# DI_DO.net
KiCad netlist of a schematic drawn in Altium Designer
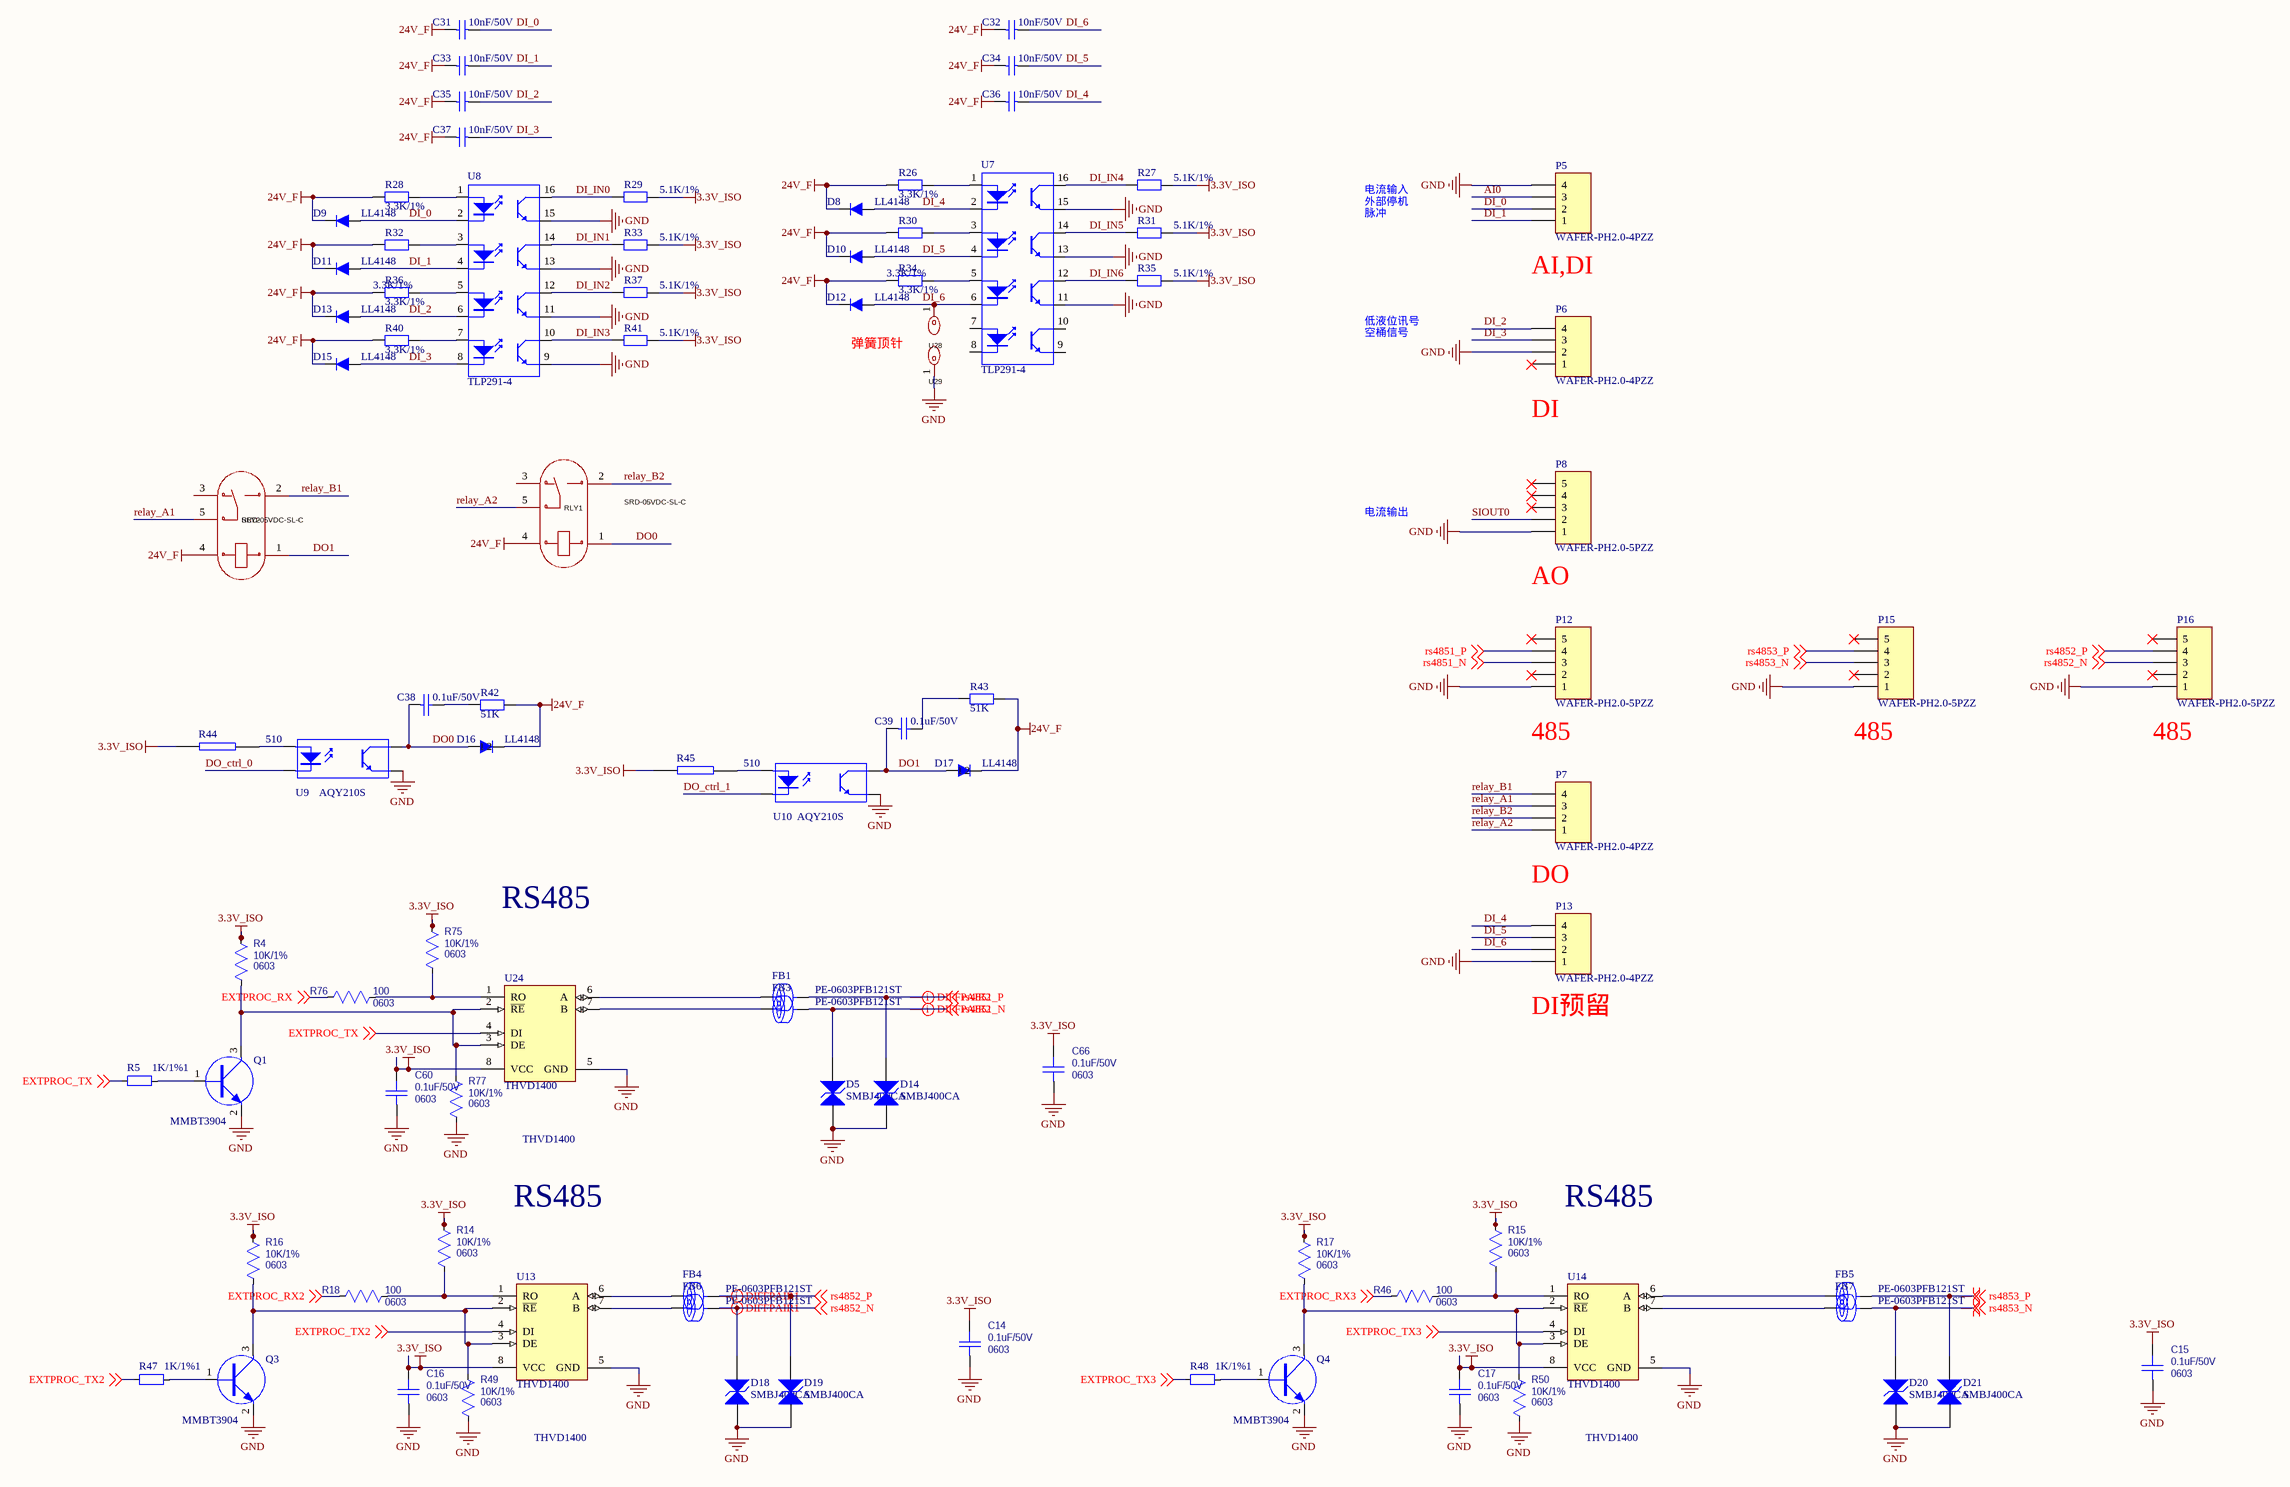
[diagram p0: DI_DO.SchDoc]

(export (version "E")
  (design (tool "Eeschema 10.0.6"))
  (components
    (comp (ref "C14")
      (value "0.1uF/50V")
      (footprint "0603C")
      (description "Capacitor, MLCC")
      (fields (field (name "PACKAGE") "0603"))
      (libsource (lib "Karl") (part "Capacitor_0603"))
    )
    (comp (ref "C15")
      (value "0.1uF/50V")
      (footprint "0603C")
      (description "Capacitor, MLCC")
      (fields (field (name "PACKAGE") "0603"))
      (libsource (lib "Karl") (part "Capacitor_0603"))
    )
    (comp (ref "C16")
      (value "0.1uF/50V")
      (footprint "0603C")
      (description "Capacitor, MLCC")
      (fields (field (name "PACKAGE") "0603"))
      (libsource (lib "Karl") (part "Capacitor_0603"))
    )
    (comp (ref "C17")
      (value "0.1uF/50V")
      (footprint "0603C")
      (description "Capacitor, MLCC")
      (fields (field (name "PACKAGE") "0603"))
      (libsource (lib "Karl") (part "Capacitor_0603"))
    )
    (comp (ref "C31")
      (value "10nF/50V")
      (footprint "0603C")
      (description "Capacitor")
      (libsource (lib "Miscellaneous Devices") (part "Cap"))
    )
    (comp (ref "C32")
      (value "10nF/50V")
      (footprint "0603C")
      (description "Capacitor")
      (libsource (lib "Miscellaneous Devices") (part "Cap"))
    )
    (comp (ref "C33")
      (value "10nF/50V")
      (footprint "0603C")
      (description "Capacitor")
      (libsource (lib "Miscellaneous Devices") (part "Cap"))
    )
    (comp (ref "C34")
      (value "10nF/50V")
      (footprint "0603C")
      (description "Capacitor")
      (libsource (lib "Miscellaneous Devices") (part "Cap"))
    )
    (comp (ref "C35")
      (value "10nF/50V")
      (footprint "0603C")
      (description "Capacitor")
      (libsource (lib "Miscellaneous Devices") (part "Cap"))
    )
    (comp (ref "C36")
      (value "10nF/50V")
      (footprint "0603C")
      (description "Capacitor")
      (libsource (lib "Miscellaneous Devices") (part "Cap"))
    )
    (comp (ref "C37")
      (value "10nF/50V")
      (footprint "0603C")
      (description "Capacitor")
      (libsource (lib "Miscellaneous Devices") (part "Cap"))
    )
    (comp (ref "C38")
      (value "0.1uF/50V")
      (footprint "0603C")
      (description "Capacitor")
      (libsource (lib "*") (part "CAP"))
    )
    (comp (ref "C39")
      (value "0.1uF/50V")
      (footprint "0603C")
      (description "Capacitor")
      (libsource (lib "*") (part "CAP"))
    )
    (comp (ref "C60")
      (value "0.1uF/50V")
      (footprint "0603C")
      (description "Capacitor, MLCC")
      (fields (field (name "PACKAGE") "0603"))
      (libsource (lib "Karl") (part "Capacitor_0603"))
    )
    (comp (ref "C66")
      (value "0.1uF/50V")
      (footprint "0603C")
      (description "Capacitor, MLCC")
      (fields (field (name "PACKAGE") "0603"))
      (libsource (lib "Karl") (part "Capacitor_0603"))
    )
    (comp (ref "D5")
      (value "SMBJ400CA")
      (footprint "SMB")
      (description "Transient Voltage Suppression Diode, 400 W, 33 V, -65 to 150 degC, 2-Pin SMD, RoHS, Tape and Reel")
      (libsource (lib "Bogen") (part "SMAJ12CA"))
    )
    (comp (ref "D8")
      (value "LL4148")
      (footprint "DO-213AB/LL34/MiniMELF")
      (description "VISHAY,LL4148,圆柱体MiniMELF100V/2A,ROHS")
      (libsource (lib "Device2018") (part "LL4148"))
    )
    (comp (ref "D9")
      (value "LL4148")
      (footprint "DO-213AB/LL34/MiniMELF")
      (description "VISHAY,LL4148,圆柱体MiniMELF100V/2A,ROHS")
      (libsource (lib "Device2018") (part "LL4148"))
    )
    (comp (ref "D10")
      (value "LL4148")
      (footprint "DO-213AB/LL34/MiniMELF")
      (description "VISHAY,LL4148,圆柱体MiniMELF100V/2A,ROHS")
      (libsource (lib "Device2018") (part "LL4148"))
    )
    (comp (ref "D11")
      (value "LL4148")
      (footprint "DO-213AB/LL34/MiniMELF")
      (description "VISHAY,LL4148,圆柱体MiniMELF100V/2A,ROHS")
      (libsource (lib "Device2018") (part "LL4148"))
    )
    (comp (ref "D12")
      (value "LL4148")
      (footprint "DO-213AB/LL34/MiniMELF")
      (description "VISHAY,LL4148,圆柱体MiniMELF100V/2A,ROHS")
      (libsource (lib "Device2018") (part "LL4148"))
    )
    (comp (ref "D13")
      (value "LL4148")
      (footprint "DO-213AB/LL34/MiniMELF")
      (description "VISHAY,LL4148,圆柱体MiniMELF100V/2A,ROHS")
      (libsource (lib "Device2018") (part "LL4148"))
    )
    (comp (ref "D14")
      (value "SMBJ400CA")
      (footprint "SMB")
      (description "Transient Voltage Suppression Diode, 400 W, 33 V, -65 to 150 degC, 2-Pin SMD, RoHS, Tape and Reel")
      (libsource (lib "Bogen") (part "SMAJ12CA"))
    )
    (comp (ref "D15")
      (value "LL4148")
      (footprint "DO-213AB/LL34/MiniMELF")
      (description "VISHAY,LL4148,圆柱体MiniMELF100V/2A,ROHS")
      (libsource (lib "Device2018") (part "LL4148"))
    )
    (comp (ref "D16")
      (value "LL4148")
      (footprint "DO-213AB/LL34/MiniMELF")
      (description "VISHAY,LL4148,圆柱体MiniMELF100V/2A,ROHS")
      (libsource (lib "") (part "LL4148_1"))
    )
    (comp (ref "D17")
      (value "LL4148")
      (footprint "DO-213AB/LL34/MiniMELF")
      (description "VISHAY,LL4148,圆柱体MiniMELF100V/2A,ROHS")
      (libsource (lib "") (part "LL4148_1"))
    )
    (comp (ref "D18")
      (value "SMBJ400CA")
      (footprint "SMB")
      (description "Transient Voltage Suppression Diode, 400 W, 33 V, -65 to 150 degC, 2-Pin SMD, RoHS, Tape and Reel")
      (libsource (lib "Bogen") (part "SMAJ12CA"))
    )
    (comp (ref "D19")
      (value "SMBJ400CA")
      (footprint "SMB")
      (description "Transient Voltage Suppression Diode, 400 W, 33 V, -65 to 150 degC, 2-Pin SMD, RoHS, Tape and Reel")
      (libsource (lib "Bogen") (part "SMAJ12CA"))
    )
    (comp (ref "D20")
      (value "SMBJ400CA")
      (footprint "SMB")
      (description "Transient Voltage Suppression Diode, 400 W, 33 V, -65 to 150 degC, 2-Pin SMD, RoHS, Tape and Reel")
      (libsource (lib "Bogen") (part "SMAJ12CA"))
    )
    (comp (ref "D21")
      (value "SMBJ400CA")
      (footprint "SMB")
      (description "Transient Voltage Suppression Diode, 400 W, 33 V, -65 to 150 degC, 2-Pin SMD, RoHS, Tape and Reel")
      (libsource (lib "Bogen") (part "SMAJ12CA"))
    )
    (comp (ref "FB1")
      (value "PE-0603PFB121ST")
      (footprint "FBC0603")
      (description "Ferrite Bead Chip")
      (libsource (lib "Karl") (part "FBC0603"))
    )
    (comp (ref "FB3")
      (value "PE-0603PFB121ST")
      (footprint "FBC0603")
      (description "Ferrite Bead Chip")
      (libsource (lib "Karl") (part "FBC0603"))
    )
    (comp (ref "FB4")
      (value "PE-0603PFB121ST")
      (footprint "FBC0603")
      (description "Ferrite Bead Chip")
      (libsource (lib "Karl") (part "FBC0603"))
    )
    (comp (ref "FB5")
      (value "PE-0603PFB121ST")
      (footprint "FBC0603")
      (description "Ferrite Bead Chip")
      (libsource (lib "Karl") (part "FBC0603"))
    )
    (comp (ref "FB6")
      (value "PE-0603PFB121ST")
      (footprint "FBC0603")
      (description "Ferrite Bead Chip")
      (libsource (lib "Karl") (part "FBC0603"))
    )
    (comp (ref "FB7")
      (value "PE-0603PFB121ST")
      (footprint "FBC0603")
      (description "Ferrite Bead Chip")
      (libsource (lib "Karl") (part "FBC0603"))
    )
    (comp (ref "P5")
      (value "WAFER-PH2.0-4PZZ")
      (footprint "CONN#PH2.0-4A")
      (description "Header, 4-Pin")
      (libsource (lib "Miscellaneous Connectors") (part "Header 4"))
    )
    (comp (ref "P6")
      (value "WAFER-PH2.0-4PZZ")
      (footprint "CONN#PH2.0-4A")
      (description "Header, 4-Pin")
      (libsource (lib "Miscellaneous Connectors") (part "Header 4"))
    )
    (comp (ref "P7")
      (value "WAFER-PH2.0-4PZZ")
      (footprint "CONN#PH2.0-4A")
      (description "Header, 4-Pin")
      (libsource (lib "Miscellaneous Connectors") (part "Header 4"))
    )
    (comp (ref "P8")
      (value "WAFER-PH2.0-5PZZ")
      (footprint "CONN#PH2.0-5A")
      (description "Header, 5-Pin")
      (libsource (lib "Miscellaneous Connectors") (part "Header 5"))
    )
    (comp (ref "P12")
      (value "WAFER-PH2.0-5PZZ")
      (footprint "CONN#PH2.0-5A")
      (description "Header, 5-Pin")
      (libsource (lib "Miscellaneous Connectors") (part "Header 5"))
    )
    (comp (ref "P13")
      (value "WAFER-PH2.0-4PZZ")
      (footprint "CONN#PH2.0-4A")
      (description "Header, 4-Pin")
      (libsource (lib "Miscellaneous Connectors") (part "Header 4"))
    )
    (comp (ref "P15")
      (value "WAFER-PH2.0-5PZZ")
      (footprint "CONN#PH2.0-5A")
      (description "Header, 5-Pin")
      (libsource (lib "Miscellaneous Connectors") (part "Header 5"))
    )
    (comp (ref "P16")
      (value "WAFER-PH2.0-5PZZ")
      (footprint "CONN#PH2.0-5A")
      (description "Header, 5-Pin")
      (libsource (lib "Miscellaneous Connectors") (part "Header 5"))
    )
    (comp (ref "Q1")
      (value "MMBT3904")
      (footprint "SOT23-3")
      (libsource (lib "CenLib") (part "NPN_MMBT3904"))
    )
    (comp (ref "Q3")
      (value "MMBT3904")
      (footprint "SOT23-3")
      (libsource (lib "CenLib") (part "NPN_MMBT3904"))
    )
    (comp (ref "Q4")
      (value "MMBT3904")
      (footprint "SOT23-3")
      (libsource (lib "CenLib") (part "NPN_MMBT3904"))
    )
    (comp (ref "R4")
      (value "10K/1%")
      (footprint "0603R")
      (description "Resistor, Standard")
      (fields (field (name "PACKAGE") "0603"))
      (libsource (lib "Karl") (part "Resistor_0603"))
    )
    (comp (ref "R5") (value "1K/1%1") (footprint "0603r") (libsource (lib "RC_M_D_00") (part "RES0603")))
    (comp (ref "R14")
      (value "10K/1%")
      (footprint "0603R")
      (description "Resistor, Standard")
      (fields (field (name "PACKAGE") "0603"))
      (libsource (lib "Karl") (part "Resistor_0603"))
    )
    (comp (ref "R15")
      (value "10K/1%")
      (footprint "0603R")
      (description "Resistor, Standard")
      (fields (field (name "PACKAGE") "0603"))
      (libsource (lib "Karl") (part "Resistor_0603"))
    )
    (comp (ref "R16")
      (value "10K/1%")
      (footprint "0603R")
      (description "Resistor, Standard")
      (fields (field (name "PACKAGE") "0603"))
      (libsource (lib "Karl") (part "Resistor_0603"))
    )
    (comp (ref "R17")
      (value "10K/1%")
      (footprint "0603R")
      (description "Resistor, Standard")
      (fields (field (name "PACKAGE") "0603"))
      (libsource (lib "Karl") (part "Resistor_0603"))
    )
    (comp (ref "R18")
      (value "100")
      (footprint "0603R")
      (description "Resistor, Standard")
      (fields (field (name "PACKAGE") "0603"))
      (libsource (lib "Karl") (part "Resistor_0603"))
    )
    (comp (ref "R26") (value "3.3K/1%") (footprint "0603R") (libsource (lib "MQlibrary") (part "Res0805M")))
    (comp (ref "R27") (value "5.1K/1%") (footprint "0603R") (libsource (lib "MQlibrary") (part "Res0805M")))
    (comp (ref "R28") (value "3.3K/1%") (footprint "0603R") (libsource (lib "MQlibrary") (part "Res0805M")))
    (comp (ref "R29") (value "5.1K/1%") (footprint "0603R") (libsource (lib "MQlibrary") (part "Res0805M")))
    (comp (ref "R30") (value "3.3K/1%") (footprint "0603R") (libsource (lib "MQlibrary") (part "Res0805M")))
    (comp (ref "R31") (value "5.1K/1%") (footprint "0603R") (libsource (lib "MQlibrary") (part "Res0805M")))
    (comp (ref "R32") (value "3.3K/1%") (footprint "0603R") (libsource (lib "MQlibrary") (part "Res0805M")))
    (comp (ref "R33") (value "5.1K/1%") (footprint "0603R") (libsource (lib "MQlibrary") (part "Res0805M")))
    (comp (ref "R34") (value "3.3K/1%") (footprint "0603R") (libsource (lib "MQlibrary") (part "Res0805M")))
    (comp (ref "R35") (value "5.1K/1%") (footprint "0603R") (libsource (lib "MQlibrary") (part "Res0805M")))
    (comp (ref "R36") (value "3.3K/1%") (footprint "0603R") (libsource (lib "MQlibrary") (part "Res0805M")))
    (comp (ref "R37") (value "5.1K/1%") (footprint "0603R") (libsource (lib "MQlibrary") (part "Res0805M")))
    (comp (ref "R40") (value "3.3K/1%") (footprint "0603R") (libsource (lib "MQlibrary") (part "Res0805M")))
    (comp (ref "R41") (value "5.1K/1%") (footprint "0603R") (libsource (lib "MQlibrary") (part "Res0805M")))
    (comp (ref "R42") (value "51K") (footprint "0603R") (libsource (lib "") (part "Res0805M_1")))
    (comp (ref "R43") (value "51K") (footprint "0603R") (libsource (lib "") (part "Res0805M_1")))
    (comp (ref "R44") (value "510") (footprint "0603R") (libsource (lib "*") (part "RES2")))
    (comp (ref "R45") (value "510") (footprint "0603R") (libsource (lib "*") (part "RES2")))
    (comp (ref "R46")
      (value "100")
      (footprint "0603R")
      (description "Resistor, Standard")
      (fields (field (name "PACKAGE") "0603"))
      (libsource (lib "Karl") (part "Resistor_0603"))
    )
    (comp (ref "R47") (value "1K/1%1") (footprint "0603r") (libsource (lib "RC_M_D_00") (part "RES0603")))
    (comp (ref "R48") (value "1K/1%1") (footprint "0603r") (libsource (lib "RC_M_D_00") (part "RES0603")))
    (comp (ref "R49")
      (value "10K/1%")
      (footprint "0603R")
      (description "Resistor, Standard")
      (fields (field (name "PACKAGE") "0603"))
      (libsource (lib "Karl") (part "Resistor_0603"))
    )
    (comp (ref "R50")
      (value "10K/1%")
      (footprint "0603R")
      (description "Resistor, Standard")
      (fields (field (name "PACKAGE") "0603"))
      (libsource (lib "Karl") (part "Resistor_0603"))
    )
    (comp (ref "R75")
      (value "10K/1%")
      (footprint "0603R")
      (description "Resistor, Standard")
      (fields (field (name "PACKAGE") "0603"))
      (libsource (lib "Karl") (part "Resistor_0603"))
    )
    (comp (ref "R76")
      (value "100")
      (footprint "0603R")
      (description "Resistor, Standard")
      (fields (field (name "PACKAGE") "0603"))
      (libsource (lib "Karl") (part "Resistor_0603"))
    )
    (comp (ref "R77")
      (value "10K/1%")
      (footprint "0603R")
      (description "Resistor, Standard")
      (fields (field (name "PACKAGE") "0603"))
      (libsource (lib "Karl") (part "Resistor_0603"))
    )
    (comp (ref "RLY1")
      (value "SRD-05VDC-SL-C")
      (footprint "RELAY-TH_SRD-XXVDC-XL-C")
      (libsource (lib "altium-import") (part "root_0_SRD-05VDC-SL-C_"))
    )
    (comp (ref "RLY2")
      (value "SRD-05VDC-SL-C")
      (footprint "RELAY-TH_SRD-XXVDC-XL-C")
      (libsource (lib "altium-import") (part "root_0_SRD-05VDC-SL-C_"))
    )
    (comp (ref "U7") (value "TLP291-4") (footprint "SOP16-T") (libsource (lib "DI16") (part "TLP281-4")))
    (comp (ref "U8") (value "TLP291-4") (footprint "SOP16-T") (libsource (lib "DI16") (part "TLP281-4")))
    (comp (ref "U9")
      (value "AQY210S")
      (footprint "sop4")
      (description "4-Pin Phototransistor Optocoupler")
      (libsource (lib "Miscellaneous Devices") (part "Optoisolator1"))
    )
    (comp (ref "U10")
      (value "AQY210S")
      (footprint "sop4")
      (description "4-Pin Phototransistor Optocoupler")
      (libsource (lib "Miscellaneous Devices") (part "Optoisolator1"))
    )
    (comp (ref "U13")
      (value "THVD1400")
      (footprint "MAXM-S8+4_M")
      (libsource (lib "Bogen") (part "MAX33071EASA+"))
    )
    (comp (ref "U14")
      (value "THVD1400")
      (footprint "MAXM-S8+4_M")
      (libsource (lib "Bogen") (part "MAX33071EASA+"))
    )
    (comp (ref "U24")
      (value "THVD1400")
      (footprint "MAXM-S8+4_M")
      (libsource (lib "Bogen") (part "MAX33071EASA+"))
    )
    (comp (ref "U28")
      (value "YTC1P-3015-01")
      (footprint "CONN-SMD_YTC1P-3015-01")
      (libsource (lib "Flow_Pump") (part "YTC1P-3015-01"))
    )
    (comp (ref "U29")
      (value "YTC1P-3015-01")
      (footprint "CONN-SMD_YTC1P-3015-01")
      (libsource (lib "Flow_Pump") (part "YTC1P-3015-01"))
    )
  )
  (nets
    (net (code "1") (name "/AI0") (class "Default")
      (node (ref "P5") (pin "3") (pinfunction "3_3") (pintype "passive"))
    )
    (net (code "2") (name "/DI_0") (class "Default")
      (node (ref "C31") (pin "2") (pinfunction "2_2") (pintype "passive"))
      (node (ref "D9") (pin "1") (pinfunction "2_1") (pintype "passive"))
      (node (ref "P5") (pin "2") (pinfunction "2_2") (pintype "passive"))
      (node (ref "U8") (pin "2") (pinfunction "K_2") (pintype "passive"))
    )
    (net (code "3") (name "/DI_1") (class "Default")
      (node (ref "C33") (pin "2") (pinfunction "2_2") (pintype "passive"))
      (node (ref "D11") (pin "1") (pinfunction "2_1") (pintype "passive"))
      (node (ref "P5") (pin "1") (pinfunction "1_1") (pintype "passive"))
      (node (ref "U8") (pin "4") (pinfunction "K_4") (pintype "passive"))
    )
    (net (code "4") (name "/DI_2") (class "Default")
      (node (ref "C35") (pin "2") (pinfunction "2_2") (pintype "passive"))
      (node (ref "D13") (pin "1") (pinfunction "2_1") (pintype "passive"))
      (node (ref "P6") (pin "4") (pinfunction "4_4") (pintype "passive"))
      (node (ref "U8") (pin "6") (pinfunction "K_6") (pintype "passive"))
    )
    (net (code "5") (name "/DI_3") (class "Default")
      (node (ref "C37") (pin "2") (pinfunction "2_2") (pintype "passive"))
      (node (ref "D15") (pin "1") (pinfunction "2_1") (pintype "passive"))
      (node (ref "P6") (pin "3") (pinfunction "3_3") (pintype "passive"))
      (node (ref "U8") (pin "8") (pinfunction "K_8") (pintype "passive"))
    )
    (net (code "6") (name "/DI_4") (class "Default")
      (node (ref "C36") (pin "2") (pinfunction "2_2") (pintype "passive"))
      (node (ref "D8") (pin "1") (pinfunction "2_1") (pintype "passive"))
      (node (ref "P13") (pin "4") (pinfunction "4_4") (pintype "passive"))
      (node (ref "U7") (pin "2") (pinfunction "K_2") (pintype "passive"))
    )
    (net (code "7") (name "/DI_5") (class "Default")
      (node (ref "C34") (pin "2") (pinfunction "2_2") (pintype "passive"))
      (node (ref "D10") (pin "1") (pinfunction "2_1") (pintype "passive"))
      (node (ref "P13") (pin "3") (pinfunction "3_3") (pintype "passive"))
      (node (ref "U7") (pin "4") (pinfunction "K_4") (pintype "passive"))
    )
    (net (code "8") (name "/DI_6") (class "Default")
      (node (ref "C32") (pin "2") (pinfunction "2_2") (pintype "passive"))
      (node (ref "D12") (pin "1") (pinfunction "2_1") (pintype "passive"))
      (node (ref "P13") (pin "2") (pinfunction "2_2") (pintype "passive"))
      (node (ref "U28") (pin "1") (pinfunction "1_1") (pintype "passive"))
      (node (ref "U7") (pin "6") (pinfunction "K_6") (pintype "passive"))
    )
    (net (code "9") (name "/DI_IN0") (class "Default")
      (node (ref "R29") (pin "2") (pinfunction "2_2") (pintype "passive"))
      (node (ref "U8") (pin "16") (pinfunction "C_16") (pintype "passive"))
    )
    (net (code "10") (name "/DI_IN1") (class "Default")
      (node (ref "R33") (pin "2") (pinfunction "2_2") (pintype "passive"))
      (node (ref "U8") (pin "14") (pinfunction "C_14") (pintype "passive"))
    )
    (net (code "11") (name "/DI_IN2") (class "Default")
      (node (ref "R37") (pin "2") (pinfunction "2_2") (pintype "passive"))
      (node (ref "U8") (pin "12") (pinfunction "C_12") (pintype "passive"))
    )
    (net (code "12") (name "/DI_IN3") (class "Default")
      (node (ref "R41") (pin "2") (pinfunction "2_2") (pintype "passive"))
      (node (ref "U8") (pin "10") (pinfunction "C_10") (pintype "passive"))
    )
    (net (code "13") (name "/DI_IN4") (class "Default")
      (node (ref "R27") (pin "2") (pinfunction "2_2") (pintype "passive"))
      (node (ref "U7") (pin "16") (pinfunction "C_16") (pintype "passive"))
    )
    (net (code "14") (name "/DI_IN5") (class "Default")
      (node (ref "R31") (pin "2") (pinfunction "2_2") (pintype "passive"))
      (node (ref "U7") (pin "14") (pinfunction "C_14") (pintype "passive"))
    )
    (net (code "15") (name "/DI_IN6") (class "Default")
      (node (ref "R35") (pin "2") (pinfunction "2_2") (pintype "passive"))
      (node (ref "U7") (pin "12") (pinfunction "C_12") (pintype "passive"))
    )
    (net (code "16") (name "/DO0") (class "Default")
      (node (ref "C38") (pin "1") (pinfunction "1_1") (pintype "passive"))
      (node (ref "D16") (pin "1") (pinfunction "2_1") (pintype "passive"))
      (node (ref "RLY1") (pin "1") (pinfunction "1_1") (pintype "passive"))
      (node (ref "U9") (pin "4") (pinfunction "C_4") (pintype "passive"))
    )
    (net (code "17") (name "/DO1") (class "Default")
      (node (ref "C39") (pin "1") (pinfunction "1_1") (pintype "passive"))
      (node (ref "D17") (pin "1") (pinfunction "2_1") (pintype "passive"))
      (node (ref "RLY2") (pin "1") (pinfunction "1_1") (pintype "passive"))
      (node (ref "U10") (pin "4") (pinfunction "C_4") (pintype "passive"))
    )
    (net (code "18") (name "/DO_ctrl_0") (class "Default")
      (node (ref "U9") (pin "2") (pinfunction "K_2") (pintype "passive"))
    )
    (net (code "19") (name "/DO_ctrl_1") (class "Default")
      (node (ref "U10") (pin "2") (pinfunction "K_2") (pintype "passive"))
    )
    (net (code "20") (name "/SIOUT0") (class "Default")
      (node (ref "P8") (pin "2") (pinfunction "2_2") (pintype "passive"))
    )
    (net (code "21") (name "/relay_A1") (class "Default")
      (node (ref "P7") (pin "3") (pinfunction "3_3") (pintype "passive"))
      (node (ref "RLY2") (pin "5") (pinfunction "5_5") (pintype "passive"))
    )
    (net (code "22") (name "/relay_A2") (class "Default")
      (node (ref "P7") (pin "1") (pinfunction "1_1") (pintype "passive"))
      (node (ref "RLY1") (pin "5") (pinfunction "5_5") (pintype "passive"))
    )
    (net (code "23") (name "/relay_B1") (class "Default")
      (node (ref "P7") (pin "4") (pinfunction "4_4") (pintype "passive"))
      (node (ref "RLY2") (pin "2") (pinfunction "2_2") (pintype "passive"))
    )
    (net (code "24") (name "/relay_B2") (class "Default")
      (node (ref "P7") (pin "2") (pinfunction "2_2") (pintype "passive"))
      (node (ref "RLY1") (pin "2") (pinfunction "2_2") (pintype "passive"))
    )
    (net (code "25") (name "3.3V_ISO") (class "Default")
      (node (ref "C14") (pin "1") (pinfunction "1_1") (pintype "passive"))
      (node (ref "C15") (pin "1") (pinfunction "1_1") (pintype "passive"))
      (node (ref "C16") (pin "1") (pinfunction "1_1") (pintype "passive"))
      (node (ref "C17") (pin "1") (pinfunction "1_1") (pintype "passive"))
      (node (ref "C60") (pin "1") (pinfunction "1_1") (pintype "passive"))
      (node (ref "C66") (pin "1") (pinfunction "1_1") (pintype "passive"))
      (node (ref "R14") (pin "2") (pinfunction "2_2") (pintype "passive"))
      (node (ref "R15") (pin "2") (pinfunction "2_2") (pintype "passive"))
      (node (ref "R16") (pin "2") (pinfunction "2_2") (pintype "passive"))
      (node (ref "R17") (pin "2") (pinfunction "2_2") (pintype "passive"))
      (node (ref "R27") (pin "1") (pinfunction "1_1") (pintype "passive"))
      (node (ref "R29") (pin "1") (pinfunction "1_1") (pintype "passive"))
      (node (ref "R31") (pin "1") (pinfunction "1_1") (pintype "passive"))
      (node (ref "R33") (pin "1") (pinfunction "1_1") (pintype "passive"))
      (node (ref "R35") (pin "1") (pinfunction "1_1") (pintype "passive"))
      (node (ref "R37") (pin "1") (pinfunction "1_1") (pintype "passive"))
      (node (ref "R4") (pin "2") (pinfunction "2_2") (pintype "passive"))
      (node (ref "R41") (pin "1") (pinfunction "1_1") (pintype "passive"))
      (node (ref "R44") (pin "2") (pinfunction "2_2") (pintype "passive"))
      (node (ref "R45") (pin "2") (pinfunction "2_2") (pintype "passive"))
      (node (ref "R75") (pin "2") (pinfunction "2_2") (pintype "passive"))
      (node (ref "U13") (pin "8") (pinfunction "VCC_8") (pintype "power_in"))
      (node (ref "U14") (pin "8") (pinfunction "VCC_8") (pintype "power_in"))
      (node (ref "U24") (pin "8") (pinfunction "VCC_8") (pintype "power_in"))
    )
    (net (code "26") (name "24V_F") (class "Default")
      (node (ref "C31") (pin "1") (pinfunction "1_1") (pintype "passive"))
      (node (ref "C32") (pin "1") (pinfunction "1_1") (pintype "passive"))
      (node (ref "C33") (pin "1") (pinfunction "1_1") (pintype "passive"))
      (node (ref "C34") (pin "1") (pinfunction "1_1") (pintype "passive"))
      (node (ref "C35") (pin "1") (pinfunction "1_1") (pintype "passive"))
      (node (ref "C36") (pin "1") (pinfunction "1_1") (pintype "passive"))
      (node (ref "C37") (pin "1") (pinfunction "1_1") (pintype "passive"))
      (node (ref "D10") (pin "2") (pinfunction "1_2") (pintype "passive"))
      (node (ref "D11") (pin "2") (pinfunction "1_2") (pintype "passive"))
      (node (ref "D12") (pin "2") (pinfunction "1_2") (pintype "passive"))
      (node (ref "D13") (pin "2") (pinfunction "1_2") (pintype "passive"))
      (node (ref "D15") (pin "2") (pinfunction "1_2") (pintype "passive"))
      (node (ref "D16") (pin "2") (pinfunction "1_2") (pintype "passive"))
      (node (ref "D17") (pin "2") (pinfunction "1_2") (pintype "passive"))
      (node (ref "D8") (pin "2") (pinfunction "1_2") (pintype "passive"))
      (node (ref "D9") (pin "2") (pinfunction "1_2") (pintype "passive"))
      (node (ref "R26") (pin "2") (pinfunction "2_2") (pintype "passive"))
      (node (ref "R28") (pin "2") (pinfunction "2_2") (pintype "passive"))
      (node (ref "R30") (pin "2") (pinfunction "2_2") (pintype "passive"))
      (node (ref "R32") (pin "2") (pinfunction "2_2") (pintype "passive"))
      (node (ref "R34") (pin "2") (pinfunction "2_2") (pintype "passive"))
      (node (ref "R36") (pin "2") (pinfunction "2_2") (pintype "passive"))
      (node (ref "R40") (pin "2") (pinfunction "2_2") (pintype "passive"))
      (node (ref "R42") (pin "2") (pinfunction "2_2") (pintype "passive"))
      (node (ref "R43") (pin "2") (pinfunction "2_2") (pintype "passive"))
      (node (ref "RLY1") (pin "4") (pinfunction "4_4") (pintype "passive"))
      (node (ref "RLY2") (pin "4") (pinfunction "4_4") (pintype "passive"))
    )
    (net (code "27") (name "EXTPROC_RX") (class "Default")
      (node (ref "R76") (pin "2") (pinfunction "2_2") (pintype "passive"))
    )
    (net (code "28") (name "EXTPROC_RX2") (class "Default")
      (node (ref "R18") (pin "2") (pinfunction "2_2") (pintype "passive"))
    )
    (net (code "29") (name "EXTPROC_RX3") (class "Default")
      (node (ref "R46") (pin "2") (pinfunction "2_2") (pintype "passive"))
    )
    (net (code "30") (name "EXTPROC_TX") (class "Default")
      (node (ref "R5") (pin "1") (pinfunction "1_1") (pintype "passive"))
      (node (ref "U24") (pin "4") (pinfunction "DI_4") (pintype "input"))
    )
    (net (code "31") (name "EXTPROC_TX2") (class "Default")
      (node (ref "R47") (pin "1") (pinfunction "1_1") (pintype "passive"))
      (node (ref "U13") (pin "4") (pinfunction "DI_4") (pintype "input"))
    )
    (net (code "32") (name "EXTPROC_TX3") (class "Default")
      (node (ref "R48") (pin "1") (pinfunction "1_1") (pintype "passive"))
      (node (ref "U14") (pin "4") (pinfunction "DI_4") (pintype "input"))
    )
    (net (code "33") (name "GND") (class "Default")
      (node (ref "C14") (pin "2") (pinfunction "2_2") (pintype "passive"))
      (node (ref "C15") (pin "2") (pinfunction "2_2") (pintype "passive"))
      (node (ref "C16") (pin "2") (pinfunction "2_2") (pintype "passive"))
      (node (ref "C17") (pin "2") (pinfunction "2_2") (pintype "passive"))
      (node (ref "C60") (pin "2") (pinfunction "2_2") (pintype "passive"))
      (node (ref "C66") (pin "2") (pinfunction "2_2") (pintype "passive"))
      (node (ref "D14") (pin "1") (pinfunction "A_1") (pintype "passive"))
      (node (ref "D18") (pin "1") (pinfunction "A_1") (pintype "passive"))
      (node (ref "D19") (pin "1") (pinfunction "A_1") (pintype "passive"))
      (node (ref "D20") (pin "1") (pinfunction "A_1") (pintype "passive"))
      (node (ref "D21") (pin "1") (pinfunction "A_1") (pintype "passive"))
      (node (ref "D5") (pin "1") (pinfunction "A_1") (pintype "passive"))
      (node (ref "P12") (pin "1") (pinfunction "1_1") (pintype "passive"))
      (node (ref "P13") (pin "1") (pinfunction "1_1") (pintype "passive"))
      (node (ref "P15") (pin "1") (pinfunction "1_1") (pintype "passive"))
      (node (ref "P16") (pin "1") (pinfunction "1_1") (pintype "passive"))
      (node (ref "P5") (pin "4") (pinfunction "4_4") (pintype "passive"))
      (node (ref "P6") (pin "2") (pinfunction "2_2") (pintype "passive"))
      (node (ref "P8") (pin "1") (pinfunction "1_1") (pintype "passive"))
      (node (ref "Q1") (pin "2") (pinfunction "E_2") (pintype "passive"))
      (node (ref "Q3") (pin "2") (pinfunction "E_2") (pintype "passive"))
      (node (ref "Q4") (pin "2") (pinfunction "E_2") (pintype "passive"))
      (node (ref "R49") (pin "1") (pinfunction "1_1") (pintype "passive"))
      (node (ref "R50") (pin "1") (pinfunction "1_1") (pintype "passive"))
      (node (ref "R77") (pin "1") (pinfunction "1_1") (pintype "passive"))
      (node (ref "U10") (pin "3") (pinfunction "E_3") (pintype "passive"))
      (node (ref "U13") (pin "5") (pinfunction "GND_5") (pintype "power_in"))
      (node (ref "U14") (pin "5") (pinfunction "GND_5") (pintype "power_in"))
      (node (ref "U24") (pin "5") (pinfunction "GND_5") (pintype "power_in"))
      (node (ref "U29") (pin "1") (pinfunction "1_1") (pintype "passive"))
      (node (ref "U7") (pin "11") (pinfunction "E_11") (pintype "passive"))
      (node (ref "U7") (pin "13") (pinfunction "E_13") (pintype "passive"))
      (node (ref "U7") (pin "15") (pinfunction "E_15") (pintype "passive"))
      (node (ref "U8") (pin "11") (pinfunction "E_11") (pintype "passive"))
      (node (ref "U8") (pin "13") (pinfunction "E_13") (pintype "passive"))
      (node (ref "U8") (pin "15") (pinfunction "E_15") (pintype "passive"))
      (node (ref "U8") (pin "9") (pinfunction "E_9") (pintype "passive"))
      (node (ref "U9") (pin "3") (pinfunction "E_3") (pintype "passive"))
    )
    (net (code "34") (name "Net-(C38-Pad2)") (class "Default")
      (node (ref "C38") (pin "2") (pinfunction "2_2") (pintype "passive"))
      (node (ref "R42") (pin "1") (pinfunction "1_1") (pintype "passive"))
    )
    (net (code "35") (name "Net-(C39-Pad2)") (class "Default")
      (node (ref "C39") (pin "2") (pinfunction "2_2") (pintype "passive"))
      (node (ref "R43") (pin "1") (pinfunction "1_1") (pintype "passive"))
    )
    (net (code "36") (name "Net-(Q1-B)") (class "Default")
      (node (ref "Q1") (pin "1") (pinfunction "B_1") (pintype "passive"))
      (node (ref "R5") (pin "2") (pinfunction "2_2") (pintype "passive"))
    )
    (net (code "37") (name "Net-(Q1-C)") (class "Default")
      (node (ref "Q1") (pin "3") (pinfunction "C_3") (pintype "passive"))
      (node (ref "R4") (pin "1") (pinfunction "1_1") (pintype "passive"))
      (node (ref "R77") (pin "2") (pinfunction "2_2") (pintype "passive"))
      (node (ref "U24") (pin "2") (pinfunction "~{RE}_2") (pintype "input"))
      (node (ref "U24") (pin "3") (pinfunction "DE_3") (pintype "input"))
    )
    (net (code "38") (name "Net-(Q3-B)") (class "Default")
      (node (ref "Q3") (pin "1") (pinfunction "B_1") (pintype "passive"))
      (node (ref "R47") (pin "2") (pinfunction "2_2") (pintype "passive"))
    )
    (net (code "39") (name "Net-(Q3-C)") (class "Default")
      (node (ref "Q3") (pin "3") (pinfunction "C_3") (pintype "passive"))
      (node (ref "R16") (pin "1") (pinfunction "1_1") (pintype "passive"))
      (node (ref "R49") (pin "2") (pinfunction "2_2") (pintype "passive"))
      (node (ref "U13") (pin "2") (pinfunction "~{RE}_2") (pintype "input"))
      (node (ref "U13") (pin "3") (pinfunction "DE_3") (pintype "input"))
    )
    (net (code "40") (name "Net-(Q4-B)") (class "Default")
      (node (ref "Q4") (pin "1") (pinfunction "B_1") (pintype "passive"))
      (node (ref "R48") (pin "2") (pinfunction "2_2") (pintype "passive"))
    )
    (net (code "41") (name "Net-(Q4-C)") (class "Default")
      (node (ref "Q4") (pin "3") (pinfunction "C_3") (pintype "passive"))
      (node (ref "R17") (pin "1") (pinfunction "1_1") (pintype "passive"))
      (node (ref "R50") (pin "2") (pinfunction "2_2") (pintype "passive"))
      (node (ref "U14") (pin "2") (pinfunction "~{RE}_2") (pintype "input"))
      (node (ref "U14") (pin "3") (pinfunction "DE_3") (pintype "input"))
    )
    (net (code "42") (name "Net-(R26-Pad1)") (class "Default")
      (node (ref "R26") (pin "1") (pinfunction "1_1") (pintype "passive"))
      (node (ref "U7") (pin "1") (pinfunction "A_1") (pintype "passive"))
    )
    (net (code "43") (name "Net-(R28-Pad1)") (class "Default")
      (node (ref "R28") (pin "1") (pinfunction "1_1") (pintype "passive"))
      (node (ref "U8") (pin "1") (pinfunction "A_1") (pintype "passive"))
    )
    (net (code "44") (name "Net-(R30-Pad1)") (class "Default")
      (node (ref "R30") (pin "1") (pinfunction "1_1") (pintype "passive"))
      (node (ref "U7") (pin "3") (pinfunction "A_3") (pintype "passive"))
    )
    (net (code "45") (name "Net-(R32-Pad1)") (class "Default")
      (node (ref "R32") (pin "1") (pinfunction "1_1") (pintype "passive"))
      (node (ref "U8") (pin "3") (pinfunction "A_3") (pintype "passive"))
    )
    (net (code "46") (name "Net-(R34-Pad1)") (class "Default")
      (node (ref "R34") (pin "1") (pinfunction "1_1") (pintype "passive"))
      (node (ref "U7") (pin "5") (pinfunction "A_5") (pintype "passive"))
    )
    (net (code "47") (name "Net-(R36-Pad1)") (class "Default")
      (node (ref "R36") (pin "1") (pinfunction "1_1") (pintype "passive"))
      (node (ref "U8") (pin "5") (pinfunction "A_5") (pintype "passive"))
    )
    (net (code "48") (name "Net-(R40-Pad1)") (class "Default")
      (node (ref "R40") (pin "1") (pinfunction "1_1") (pintype "passive"))
      (node (ref "U8") (pin "7") (pinfunction "A_7") (pintype "passive"))
    )
    (net (code "49") (name "Net-(U9-A)") (class "Default")
      (node (ref "R44") (pin "1") (pinfunction "1_1") (pintype "passive"))
      (node (ref "U9") (pin "1") (pinfunction "A_1") (pintype "passive"))
    )
    (net (code "50") (name "Net-(U10-A)") (class "Default")
      (node (ref "R45") (pin "1") (pinfunction "1_1") (pintype "passive"))
      (node (ref "U10") (pin "1") (pinfunction "A_1") (pintype "passive"))
    )
    (net (code "51") (name "Net-(U13-A)") (class "Default")
      (node (ref "FB4") (pin "1") (pinfunction "1_1") (pintype "passive"))
      (node (ref "U13") (pin "6") (pinfunction "A_6") (pintype "bidirectional"))
    )
    (net (code "52") (name "Net-(U13-B)") (class "Default")
      (node (ref "FB6") (pin "1") (pinfunction "1_1") (pintype "passive"))
      (node (ref "U13") (pin "7") (pinfunction "B_7") (pintype "bidirectional"))
    )
    (net (code "53") (name "Net-(U13-RO)") (class "Default")
      (node (ref "R14") (pin "1") (pinfunction "1_1") (pintype "passive"))
      (node (ref "R18") (pin "1") (pinfunction "1_1") (pintype "passive"))
      (node (ref "U13") (pin "1") (pinfunction "RO_1") (pintype "tri_state"))
    )
    (net (code "54") (name "Net-(U14-A)") (class "Default")
      (node (ref "FB5") (pin "1") (pinfunction "1_1") (pintype "passive"))
      (node (ref "U14") (pin "6") (pinfunction "A_6") (pintype "bidirectional"))
    )
    (net (code "55") (name "Net-(U14-B)") (class "Default")
      (node (ref "FB7") (pin "1") (pinfunction "1_1") (pintype "passive"))
      (node (ref "U14") (pin "7") (pinfunction "B_7") (pintype "bidirectional"))
    )
    (net (code "56") (name "Net-(U14-RO)") (class "Default")
      (node (ref "R15") (pin "1") (pinfunction "1_1") (pintype "passive"))
      (node (ref "R46") (pin "1") (pinfunction "1_1") (pintype "passive"))
      (node (ref "U14") (pin "1") (pinfunction "RO_1") (pintype "tri_state"))
    )
    (net (code "57") (name "Net-(U24-A)") (class "Default")
      (node (ref "FB1") (pin "1") (pinfunction "1_1") (pintype "passive"))
      (node (ref "U24") (pin "6") (pinfunction "A_6") (pintype "bidirectional"))
    )
    (net (code "58") (name "Net-(U24-B)") (class "Default")
      (node (ref "FB3") (pin "1") (pinfunction "1_1") (pintype "passive"))
      (node (ref "U24") (pin "7") (pinfunction "B_7") (pintype "bidirectional"))
    )
    (net (code "59") (name "Net-(U24-RO)") (class "Default")
      (node (ref "R75") (pin "1") (pinfunction "1_1") (pintype "passive"))
      (node (ref "R76") (pin "1") (pinfunction "1_1") (pintype "passive"))
      (node (ref "U24") (pin "1") (pinfunction "RO_1") (pintype "tri_state"))
    )
    (net (code "60") (name "rs4851_N") (class "Default")
      (node (ref "D5") (pin "2") (pinfunction "A_2") (pintype "passive"))
      (node (ref "FB3") (pin "2") (pinfunction "2_2") (pintype "passive"))
      (node (ref "P12") (pin "3") (pinfunction "3_3") (pintype "passive"))
    )
    (net (code "61") (name "rs4851_P") (class "Default")
      (node (ref "D14") (pin "2") (pinfunction "A_2") (pintype "passive"))
      (node (ref "FB1") (pin "2") (pinfunction "2_2") (pintype "passive"))
      (node (ref "P12") (pin "4") (pinfunction "4_4") (pintype "passive"))
    )
    (net (code "62") (name "rs4852_N") (class "Default")
      (node (ref "D18") (pin "2") (pinfunction "A_2") (pintype "passive"))
      (node (ref "FB6") (pin "2") (pinfunction "2_2") (pintype "passive"))
      (node (ref "P16") (pin "3") (pinfunction "3_3") (pintype "passive"))
    )
    (net (code "63") (name "rs4852_P") (class "Default")
      (node (ref "D19") (pin "2") (pinfunction "A_2") (pintype "passive"))
      (node (ref "FB4") (pin "2") (pinfunction "2_2") (pintype "passive"))
      (node (ref "P16") (pin "4") (pinfunction "4_4") (pintype "passive"))
    )
    (net (code "64") (name "rs4853_N") (class "Default")
      (node (ref "D20") (pin "2") (pinfunction "A_2") (pintype "passive"))
      (node (ref "FB7") (pin "2") (pinfunction "2_2") (pintype "passive"))
      (node (ref "P15") (pin "3") (pinfunction "3_3") (pintype "passive"))
    )
    (net (code "65") (name "rs4853_P") (class "Default")
      (node (ref "D21") (pin "2") (pinfunction "A_2") (pintype "passive"))
      (node (ref "FB5") (pin "2") (pinfunction "2_2") (pintype "passive"))
      (node (ref "P15") (pin "4") (pinfunction "4_4") (pintype "passive"))
    )
    (net (code "66") (name "unconnected-(P6-Pad1)") (class "Default")
      (node (ref "P6") (pin "1") (pinfunction "1_1") (pintype "passive+no_connect"))
    )
    (net (code "67") (name "unconnected-(P8-Pad3)") (class "Default")
      (node (ref "P8") (pin "3") (pinfunction "3_3") (pintype "passive+no_connect"))
    )
    (net (code "68") (name "unconnected-(P8-Pad4)") (class "Default")
      (node (ref "P8") (pin "4") (pinfunction "4_4") (pintype "passive+no_connect"))
    )
    (net (code "69") (name "unconnected-(P8-Pad5)") (class "Default")
      (node (ref "P8") (pin "5") (pinfunction "5_5") (pintype "passive+no_connect"))
    )
    (net (code "70") (name "unconnected-(P12-Pad2)") (class "Default")
      (node (ref "P12") (pin "2") (pinfunction "2_2") (pintype "passive+no_connect"))
    )
    (net (code "71") (name "unconnected-(P12-Pad5)") (class "Default")
      (node (ref "P12") (pin "5") (pinfunction "5_5") (pintype "passive+no_connect"))
    )
    (net (code "72") (name "unconnected-(P15-Pad2)") (class "Default")
      (node (ref "P15") (pin "2") (pinfunction "2_2") (pintype "passive+no_connect"))
    )
    (net (code "73") (name "unconnected-(P15-Pad5)") (class "Default")
      (node (ref "P15") (pin "5") (pinfunction "5_5") (pintype "passive+no_connect"))
    )
    (net (code "74") (name "unconnected-(P16-Pad2)") (class "Default")
      (node (ref "P16") (pin "2") (pinfunction "2_2") (pintype "passive+no_connect"))
    )
    (net (code "75") (name "unconnected-(P16-Pad5)") (class "Default")
      (node (ref "P16") (pin "5") (pinfunction "5_5") (pintype "passive+no_connect"))
    )
    (net (code "76") (name "unconnected-(RLY1-Pad3)") (class "Default")
      (node (ref "RLY1") (pin "3") (pinfunction "3_3") (pintype "passive"))
    )
    (net (code "77") (name "unconnected-(RLY2-Pad3)") (class "Default")
      (node (ref "RLY2") (pin "3") (pinfunction "3_3") (pintype "passive"))
    )
    (net (code "78") (name "unconnected-(U7-A-Pad7)") (class "Default")
      (node (ref "U7") (pin "7") (pinfunction "A_7") (pintype "passive"))
    )
    (net (code "79") (name "unconnected-(U7-C-Pad10)") (class "Default")
      (node (ref "U7") (pin "10") (pinfunction "C_10") (pintype "passive"))
    )
    (net (code "80") (name "unconnected-(U7-E-Pad9)") (class "Default")
      (node (ref "U7") (pin "9") (pinfunction "E_9") (pintype "passive"))
    )
    (net (code "81") (name "unconnected-(U7-K-Pad8)") (class "Default")
      (node (ref "U7") (pin "8") (pinfunction "K_8") (pintype "passive"))
    )
  )
)
